# servoUART_by_Raspberry_Pi3_V2.net
KiCad netlist of a schematic drawn in EAGLE
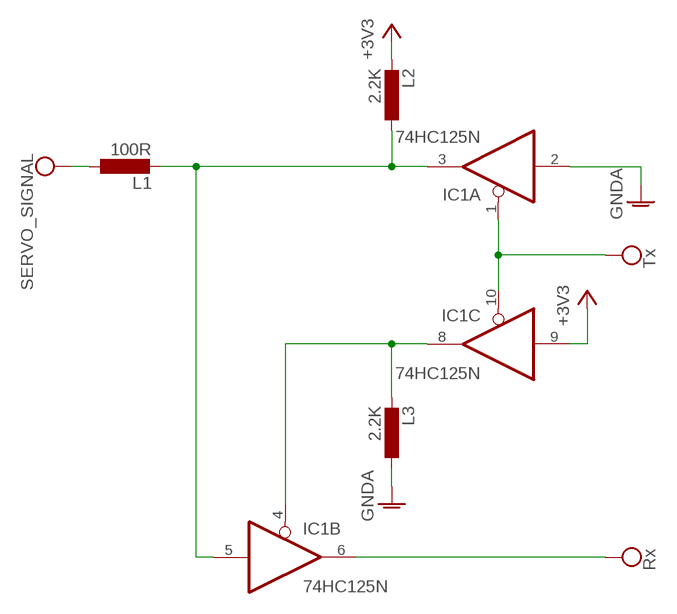
[diagram p0: schematic, sheet 1]

(export (version "E")
  (design (tool "Eeschema 10.0.6"))
  (components
    (comp (ref "IC1")
      (value "74HC125N")
      (footprint "eagle-import:DIL14")
      (libsource (lib "eagle-import") (part "74125NHC"))
    )
    (comp (ref "L1")
      (value "100R")
      (footprint "eagle-import:0204_5")
      (libsource (lib "eagle-import") (part "L-EU0204/5"))
    )
    (comp (ref "L2")
      (value "2.2K")
      (footprint "eagle-import:0204_5")
      (libsource (lib "eagle-import") (part "L-EU0204/5"))
    )
    (comp (ref "L3")
      (value "2.2K")
      (footprint "eagle-import:0204_5")
      (libsource (lib "eagle-import") (part "L-EU0204/5"))
    )
  )
  (nets
    (net (code "1") (name "+3V3") (class "Default")
      (node (ref "IC1") (pin "9") (pinfunction "I_9") (pintype "input"))
      (node (ref "L2") (pin "2") (pinfunction "2_2") (pintype "passive"))
    )
    (net (code "2") (name "GNDA") (class "Default")
      (node (ref "IC1") (pin "2") (pinfunction "I_2") (pintype "input"))
      (node (ref "L3") (pin "1") (pinfunction "1_1") (pintype "passive"))
    )
    (net (code "3") (name "Net-(IC1A-O)") (class "Default")
      (node (ref "IC1") (pin "3") (pinfunction "O_3") (pintype "tri_state"))
      (node (ref "IC1") (pin "5") (pinfunction "I_5") (pintype "input"))
      (node (ref "L1") (pin "2") (pinfunction "2_2") (pintype "passive"))
      (node (ref "L2") (pin "1") (pinfunction "1_1") (pintype "passive"))
    )
    (net (code "4") (name "Net-(IC1B-OE)") (class "Default")
      (node (ref "IC1") (pin "4") (pinfunction "OE_4") (pintype "input"))
      (node (ref "IC1") (pin "8") (pinfunction "O_8") (pintype "tri_state"))
      (node (ref "L3") (pin "2") (pinfunction "2_2") (pintype "passive"))
    )
    (net (code "5") (name "Rx") (class "Default")
      (node (ref "IC1") (pin "1") (pinfunction "OE_1") (pintype "input"))
      (node (ref "IC1") (pin "10") (pinfunction "OE_10") (pintype "input"))
      (node (ref "IC1") (pin "6") (pinfunction "O_6") (pintype "tri_state"))
      (node (ref "L1") (pin "1") (pinfunction "1_1") (pintype "passive"))
    )
  )
)
